# Sheet1.net
KiCad netlist of a schematic drawn in Altium Designer
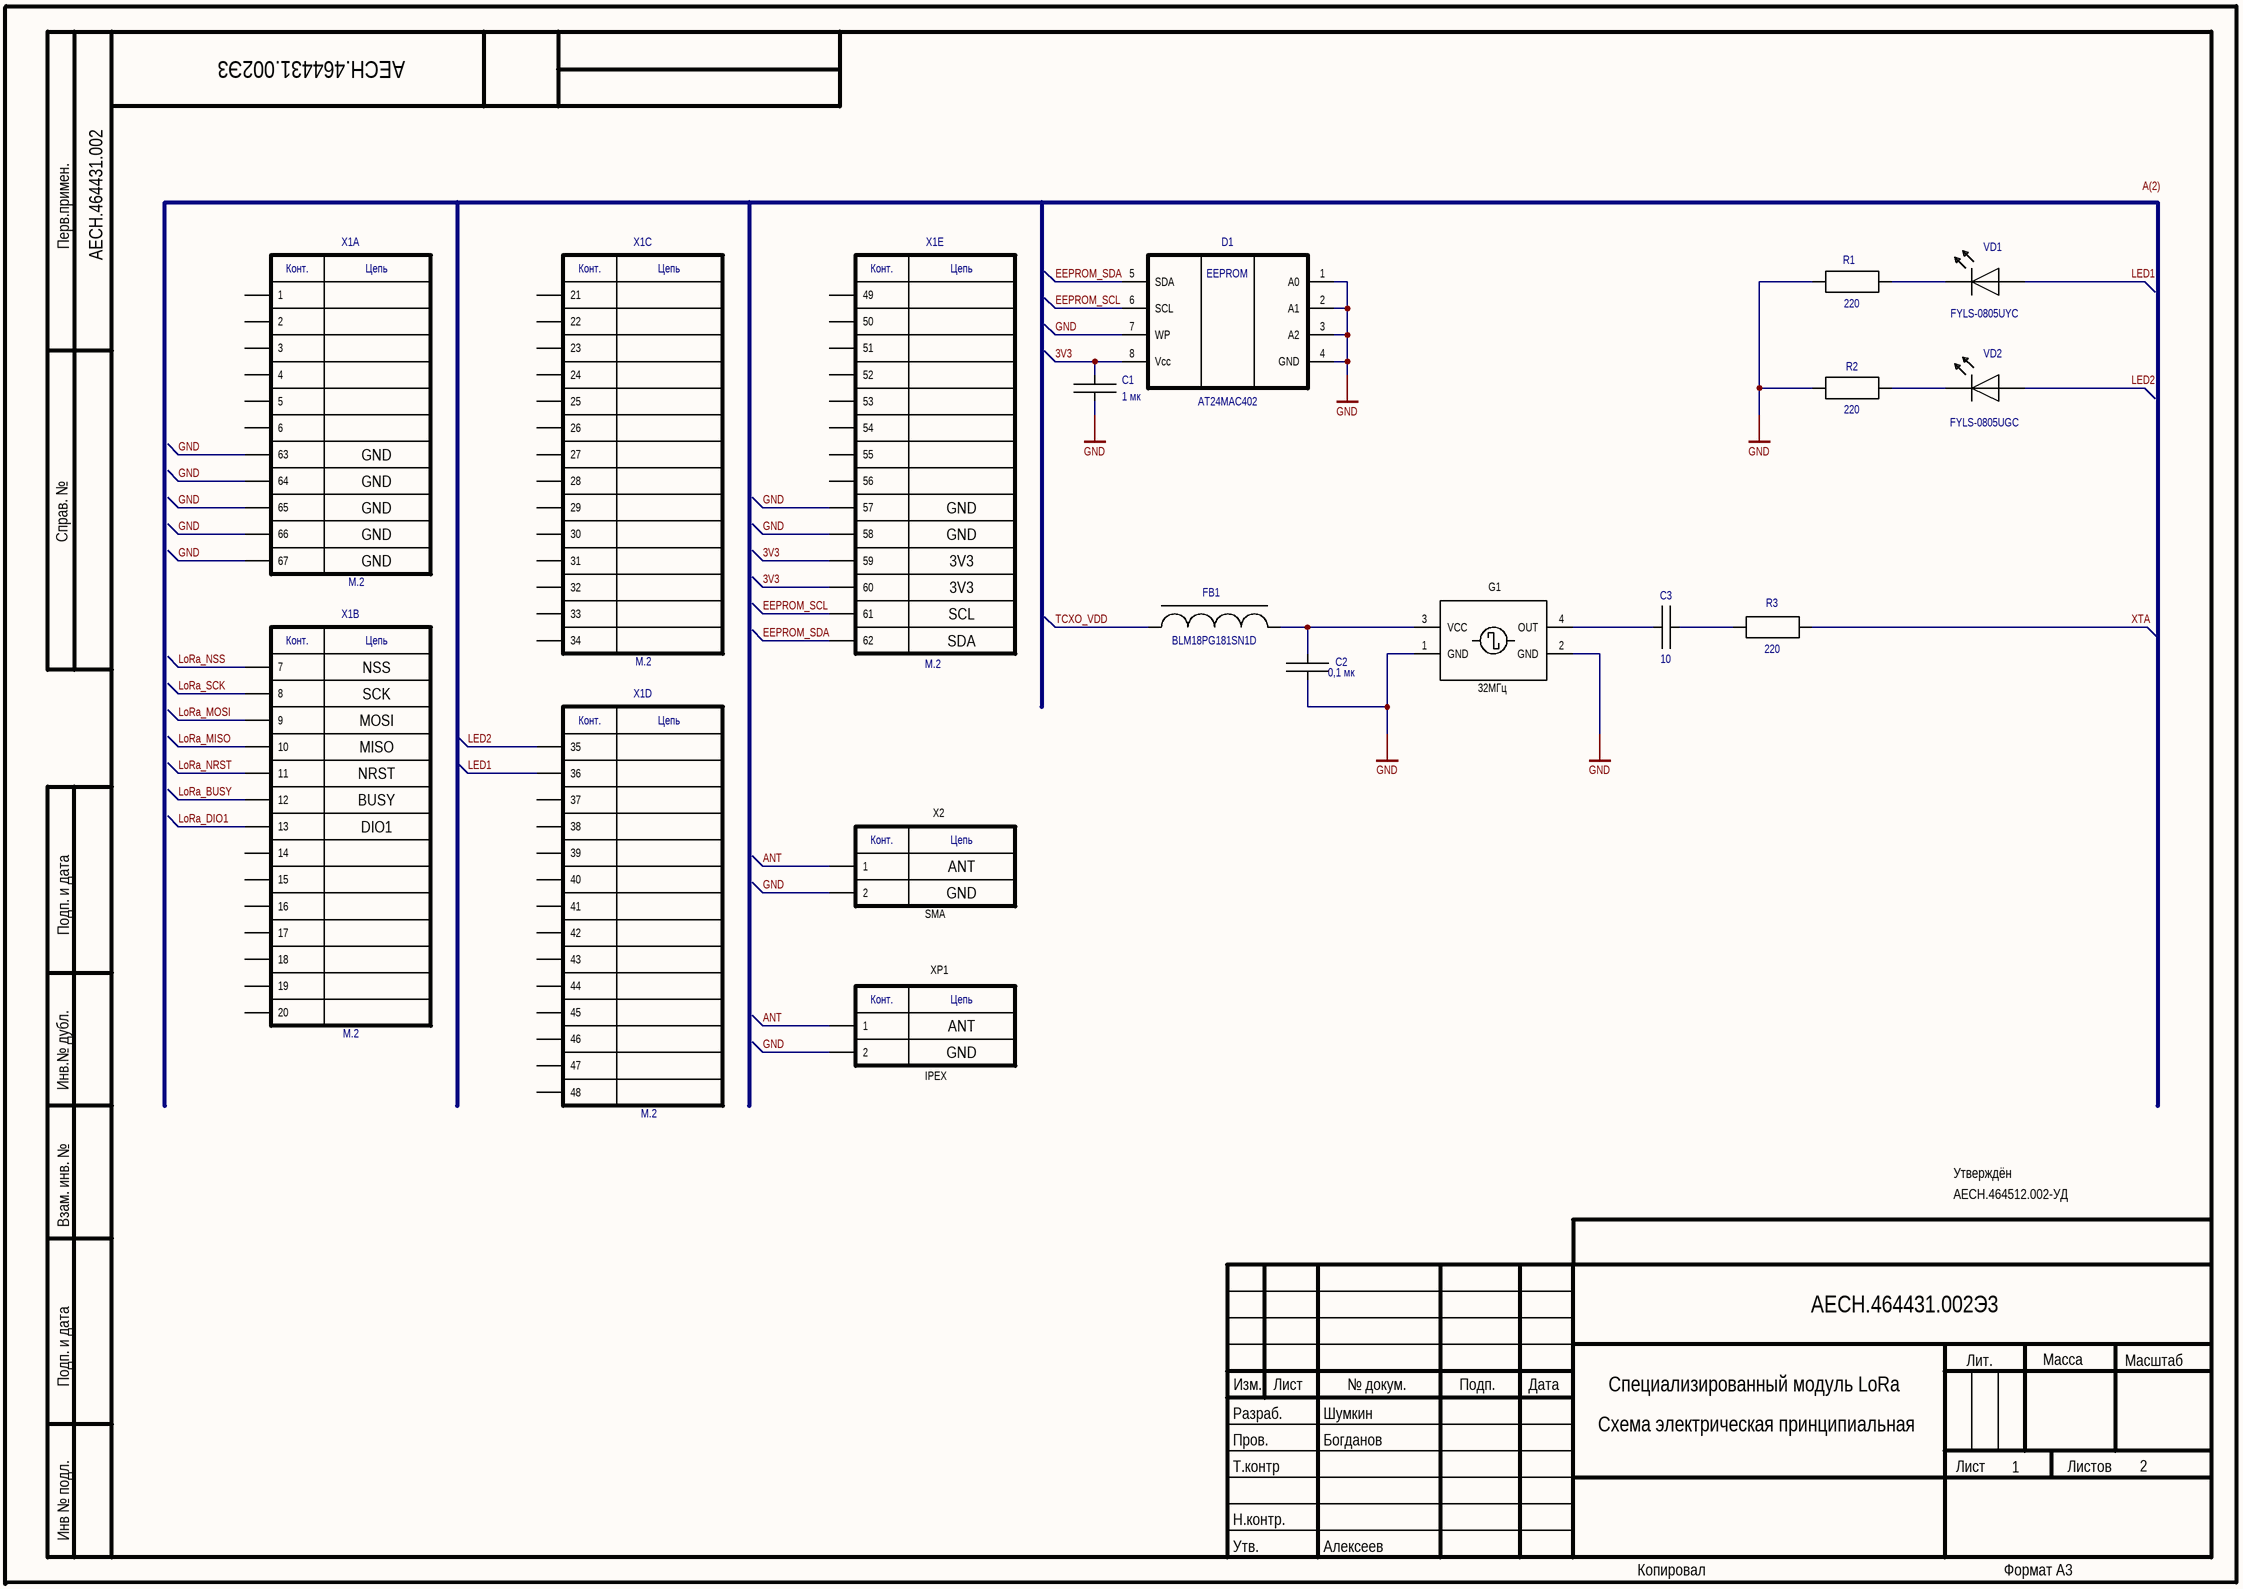
[diagram p0: Sheet1.SchDoc]

(export (version "E")
  (design (tool "Eeschema 10.0.6"))
  (components
    (comp (ref "C1")
      (value "1 мк")
      (footprint "С0603")
      (fields (field (name "VOLTAGE") "16 В") (field (name "Comment") "C"))
      (libsource (lib "Schlib1") (part "C"))
    )
    (comp (ref "C2")
      (value "0,1 мк")
      (footprint "С0603")
      (fields (field (name "VOLTAGE") "16 В") (field (name "Comment") "C"))
      (libsource (lib "Schlib1") (part "C"))
    )
    (comp (ref "C3")
      (value "10")
      (footprint "С0603")
      (fields (field (name "VOLTAGE") "50 В") (field (name "Comment") "C"))
      (libsource (lib "Schlib1") (part "C"))
    )
    (comp (ref "D1") (value "AT24MAC402") (footprint "SOIC8") (libsource (lib "Schlib1") (part "AT24MAC402")))
    (comp (ref "FB1")
      (value "BLM18PG181SN1D")
      (footprint "R0603")
      (fields (field (name "Comment") "Ferrite_Beads"))
      (libsource (lib "Schlib1") (part "Ferrite_Beads"))
    )
    (comp (ref "G1") (value "32МГц") (footprint "OSC_2016") (libsource (lib "Schlib1") (part "TCXO")))
    (comp (ref "R1")
      (value "220")
      (footprint "R0603")
      (fields (field (name "Comment") "R"))
      (libsource (lib "Schlib1") (part "R"))
    )
    (comp (ref "R2")
      (value "220")
      (footprint "R0603")
      (fields (field (name "Comment") "R"))
      (libsource (lib "Schlib1") (part "R"))
    )
    (comp (ref "R3")
      (value "220")
      (footprint "R0603")
      (fields (field (name "Comment") "R"))
      (libsource (lib "Schlib1") (part "R"))
    )
    (comp (ref "VD1")
      (value "FYLS-0805UYC")
      (footprint "LED_0805")
      (fields (field (name "VOLTAGE") "?"))
      (libsource (lib "Schlib1") (part "VD_LED"))
    )
    (comp (ref "VD2")
      (value "FYLS-0805UGC")
      (footprint "LED_0805")
      (fields (field (name "VOLTAGE") "?"))
      (libsource (lib "Schlib1") (part "VD_LED"))
    )
    (comp (ref "X1") (value "M.2") (footprint "M.2_edge") (libsource (lib "Schlib1") (part "M.2")))
    (comp (ref "X2") (value "SMA") (footprint "SMA_kont") (libsource (lib "Schlib1") (part "2pin")))
    (comp (ref "XP1") (value "IPEX") (footprint "IPEX") (libsource (lib "Schlib1") (part "2pin")))
  )
  (nets
    (net (code "1") (name "/3V3") (class "Default")
      (node (ref "C1") (pin "1") (pinfunction "1_1") (pintype "passive"))
      (node (ref "D1") (pin "8") (pinfunction "Vcc_8") (pintype "passive"))
      (node (ref "X1") (pin "59") (pinfunction "59_59") (pintype "passive"))
      (node (ref "X1") (pin "60") (pinfunction "60_60") (pintype "passive"))
    )
    (net (code "3") (name "/ANT") (class "Default")
      (node (ref "X2") (pin "1") (pinfunction "1_1") (pintype "passive"))
      (node (ref "XP1") (pin "1") (pinfunction "1_1") (pintype "passive"))
    )
    (net (code "4") (name "/EEPROM_SCL") (class "Default")
      (node (ref "D1") (pin "6") (pinfunction "SCL_6") (pintype "passive"))
      (node (ref "X1") (pin "61") (pinfunction "61_61") (pintype "passive"))
    )
    (net (code "5") (name "/EEPROM_SDA") (class "Default")
      (node (ref "D1") (pin "5") (pinfunction "SDA_5") (pintype "passive"))
      (node (ref "X1") (pin "62") (pinfunction "62_62") (pintype "passive"))
    )
    (net (code "6") (name "/LED1") (class "Default")
      (node (ref "VD1") (pin "1") (pinfunction "1_1") (pintype "passive"))
      (node (ref "X1") (pin "36") (pinfunction "36_36") (pintype "passive"))
    )
    (net (code "7") (name "/LED2") (class "Default")
      (node (ref "VD2") (pin "1") (pinfunction "1_1") (pintype "passive"))
      (node (ref "X1") (pin "35") (pinfunction "35_35") (pintype "passive"))
    )
    (net (code "8") (name "/LoRa_BUSY") (class "Default")
      (node (ref "X1") (pin "12") (pinfunction "12_12") (pintype "passive"))
    )
    (net (code "9") (name "/LoRa_DIO1") (class "Default")
      (node (ref "X1") (pin "13") (pinfunction "13_13") (pintype "passive"))
    )
    (net (code "10") (name "/LoRa_MISO") (class "Default")
      (node (ref "X1") (pin "10") (pinfunction "10_10") (pintype "passive"))
    )
    (net (code "11") (name "/LoRa_MOSI") (class "Default")
      (node (ref "X1") (pin "9") (pinfunction "9_9") (pintype "passive"))
    )
    (net (code "12") (name "/LoRa_NRST") (class "Default")
      (node (ref "X1") (pin "11") (pinfunction "11_11") (pintype "passive"))
    )
    (net (code "13") (name "/LoRa_NSS") (class "Default")
      (node (ref "X1") (pin "7") (pinfunction "7_7") (pintype "passive"))
    )
    (net (code "14") (name "/LoRa_SCK") (class "Default")
      (node (ref "X1") (pin "8") (pinfunction "8_8") (pintype "passive"))
    )
    (net (code "15") (name "/TCXO_VDD") (class "Default")
      (node (ref "FB1") (pin "1") (pinfunction "1_1") (pintype "passive"))
    )
    (net (code "16") (name "/XTA") (class "Default")
      (node (ref "R3") (pin "2") (pinfunction "2_2") (pintype "passive"))
    )
    (net (code "17") (name "GND") (class "Default")
      (node (ref "C1") (pin "2") (pinfunction "2_2") (pintype "passive"))
      (node (ref "C2") (pin "2") (pinfunction "2_2") (pintype "passive"))
      (node (ref "D1") (pin "1") (pinfunction "A0_1") (pintype "passive"))
      (node (ref "D1") (pin "2") (pinfunction "A1_2") (pintype "passive"))
      (node (ref "D1") (pin "3") (pinfunction "A2_3") (pintype "passive"))
      (node (ref "D1") (pin "4") (pinfunction "GND_4") (pintype "passive"))
      (node (ref "D1") (pin "7") (pinfunction "WP_7") (pintype "passive"))
      (node (ref "G1") (pin "1") (pinfunction "GND_1") (pintype "passive"))
      (node (ref "G1") (pin "2") (pinfunction "GND_2") (pintype "passive"))
      (node (ref "R1") (pin "2") (pinfunction "2_2") (pintype "passive"))
      (node (ref "R2") (pin "2") (pinfunction "2_2") (pintype "passive"))
      (node (ref "X1") (pin "57") (pinfunction "57_57") (pintype "passive"))
      (node (ref "X1") (pin "58") (pinfunction "58_58") (pintype "passive"))
      (node (ref "X1") (pin "63") (pinfunction "63_63") (pintype "passive"))
      (node (ref "X1") (pin "64") (pinfunction "64_64") (pintype "passive"))
      (node (ref "X1") (pin "65") (pinfunction "65_65") (pintype "passive"))
      (node (ref "X1") (pin "66") (pinfunction "66_66") (pintype "passive"))
      (node (ref "X1") (pin "67") (pinfunction "67_67") (pintype "passive"))
      (node (ref "X2") (pin "2") (pinfunction "2_2") (pintype "passive"))
      (node (ref "XP1") (pin "2") (pinfunction "2_2") (pintype "passive"))
    )
    (net (code "18") (name "Net-(C3-Pad2)") (class "Default")
      (node (ref "C3") (pin "2") (pinfunction "2_2") (pintype "passive"))
      (node (ref "R3") (pin "1") (pinfunction "1_1") (pintype "passive"))
    )
    (net (code "19") (name "Net-(G1-OUT)") (class "Default")
      (node (ref "C3") (pin "1") (pinfunction "1_1") (pintype "passive"))
      (node (ref "G1") (pin "4") (pinfunction "OUT_4") (pintype "passive"))
    )
    (net (code "20") (name "Net-(G1-VCC)") (class "Default")
      (node (ref "C2") (pin "1") (pinfunction "1_1") (pintype "passive"))
      (node (ref "FB1") (pin "2") (pinfunction "2_2") (pintype "passive"))
      (node (ref "G1") (pin "3") (pinfunction "VCC_3") (pintype "passive"))
    )
    (net (code "21") (name "Net-(R1-Pad1)") (class "Default")
      (node (ref "R1") (pin "1") (pinfunction "1_1") (pintype "passive"))
      (node (ref "VD1") (pin "2") (pinfunction "2_2") (pintype "passive"))
    )
    (net (code "22") (name "Net-(R2-Pad1)") (class "Default")
      (node (ref "R2") (pin "1") (pinfunction "1_1") (pintype "passive"))
      (node (ref "VD2") (pin "2") (pinfunction "2_2") (pintype "passive"))
    )
    (net (code "23") (name "unconnected-(X1-Pad1)") (class "Default")
      (node (ref "X1") (pin "1") (pinfunction "1_1") (pintype "passive"))
    )
    (net (code "24") (name "unconnected-(X1-Pad2)") (class "Default")
      (node (ref "X1") (pin "2") (pinfunction "2_2") (pintype "passive"))
    )
    (net (code "25") (name "unconnected-(X1-Pad3)") (class "Default")
      (node (ref "X1") (pin "3") (pinfunction "3_3") (pintype "passive"))
    )
    (net (code "26") (name "unconnected-(X1-Pad4)") (class "Default")
      (node (ref "X1") (pin "4") (pinfunction "4_4") (pintype "passive"))
    )
    (net (code "27") (name "unconnected-(X1-Pad5)") (class "Default")
      (node (ref "X1") (pin "5") (pinfunction "5_5") (pintype "passive"))
    )
    (net (code "28") (name "unconnected-(X1-Pad6)") (class "Default")
      (node (ref "X1") (pin "6") (pinfunction "6_6") (pintype "passive"))
    )
    (net (code "29") (name "unconnected-(X1-Pad14)") (class "Default")
      (node (ref "X1") (pin "14") (pinfunction "14_14") (pintype "passive"))
    )
    (net (code "30") (name "unconnected-(X1-Pad15)") (class "Default")
      (node (ref "X1") (pin "15") (pinfunction "15_15") (pintype "passive"))
    )
    (net (code "31") (name "unconnected-(X1-Pad16)") (class "Default")
      (node (ref "X1") (pin "16") (pinfunction "16_16") (pintype "passive"))
    )
    (net (code "32") (name "unconnected-(X1-Pad17)") (class "Default")
      (node (ref "X1") (pin "17") (pinfunction "17_17") (pintype "passive"))
    )
    (net (code "33") (name "unconnected-(X1-Pad18)") (class "Default")
      (node (ref "X1") (pin "18") (pinfunction "18_18") (pintype "passive"))
    )
    (net (code "34") (name "unconnected-(X1-Pad19)") (class "Default")
      (node (ref "X1") (pin "19") (pinfunction "19_19") (pintype "passive"))
    )
    (net (code "35") (name "unconnected-(X1-Pad20)") (class "Default")
      (node (ref "X1") (pin "20") (pinfunction "20_20") (pintype "passive"))
    )
    (net (code "36") (name "unconnected-(X1-Pad21)") (class "Default")
      (node (ref "X1") (pin "21") (pinfunction "21_21") (pintype "passive"))
    )
    (net (code "37") (name "unconnected-(X1-Pad22)") (class "Default")
      (node (ref "X1") (pin "22") (pinfunction "22_22") (pintype "passive"))
    )
    (net (code "38") (name "unconnected-(X1-Pad23)") (class "Default")
      (node (ref "X1") (pin "23") (pinfunction "23_23") (pintype "passive"))
    )
    (net (code "39") (name "unconnected-(X1-Pad24)") (class "Default")
      (node (ref "X1") (pin "24") (pinfunction "24_24") (pintype "passive"))
    )
    (net (code "40") (name "unconnected-(X1-Pad25)") (class "Default")
      (node (ref "X1") (pin "25") (pinfunction "25_25") (pintype "passive"))
    )
    (net (code "41") (name "unconnected-(X1-Pad26)") (class "Default")
      (node (ref "X1") (pin "26") (pinfunction "26_26") (pintype "passive"))
    )
    (net (code "42") (name "unconnected-(X1-Pad27)") (class "Default")
      (node (ref "X1") (pin "27") (pinfunction "27_27") (pintype "passive"))
    )
    (net (code "43") (name "unconnected-(X1-Pad28)") (class "Default")
      (node (ref "X1") (pin "28") (pinfunction "28_28") (pintype "passive"))
    )
    (net (code "44") (name "unconnected-(X1-Pad29)") (class "Default")
      (node (ref "X1") (pin "29") (pinfunction "29_29") (pintype "passive"))
    )
    (net (code "45") (name "unconnected-(X1-Pad30)") (class "Default")
      (node (ref "X1") (pin "30") (pinfunction "30_30") (pintype "passive"))
    )
    (net (code "46") (name "unconnected-(X1-Pad31)") (class "Default")
      (node (ref "X1") (pin "31") (pinfunction "31_31") (pintype "passive"))
    )
    (net (code "47") (name "unconnected-(X1-Pad32)") (class "Default")
      (node (ref "X1") (pin "32") (pinfunction "32_32") (pintype "passive"))
    )
    (net (code "48") (name "unconnected-(X1-Pad33)") (class "Default")
      (node (ref "X1") (pin "33") (pinfunction "33_33") (pintype "passive"))
    )
    (net (code "49") (name "unconnected-(X1-Pad34)") (class "Default")
      (node (ref "X1") (pin "34") (pinfunction "34_34") (pintype "passive"))
    )
    (net (code "50") (name "unconnected-(X1-Pad37)") (class "Default")
      (node (ref "X1") (pin "37") (pinfunction "37_37") (pintype "passive"))
    )
    (net (code "51") (name "unconnected-(X1-Pad38)") (class "Default")
      (node (ref "X1") (pin "38") (pinfunction "38_38") (pintype "passive"))
    )
    (net (code "52") (name "unconnected-(X1-Pad39)") (class "Default")
      (node (ref "X1") (pin "39") (pinfunction "39_39") (pintype "passive"))
    )
    (net (code "53") (name "unconnected-(X1-Pad40)") (class "Default")
      (node (ref "X1") (pin "40") (pinfunction "40_40") (pintype "passive"))
    )
    (net (code "54") (name "unconnected-(X1-Pad41)") (class "Default")
      (node (ref "X1") (pin "41") (pinfunction "41_41") (pintype "passive"))
    )
    (net (code "55") (name "unconnected-(X1-Pad42)") (class "Default")
      (node (ref "X1") (pin "42") (pinfunction "42_42") (pintype "passive"))
    )
    (net (code "56") (name "unconnected-(X1-Pad43)") (class "Default")
      (node (ref "X1") (pin "43") (pinfunction "43_43") (pintype "passive"))
    )
    (net (code "57") (name "unconnected-(X1-Pad44)") (class "Default")
      (node (ref "X1") (pin "44") (pinfunction "44_44") (pintype "passive"))
    )
    (net (code "58") (name "unconnected-(X1-Pad45)") (class "Default")
      (node (ref "X1") (pin "45") (pinfunction "45_45") (pintype "passive"))
    )
    (net (code "59") (name "unconnected-(X1-Pad46)") (class "Default")
      (node (ref "X1") (pin "46") (pinfunction "46_46") (pintype "passive"))
    )
    (net (code "60") (name "unconnected-(X1-Pad47)") (class "Default")
      (node (ref "X1") (pin "47") (pinfunction "47_47") (pintype "passive"))
    )
    (net (code "61") (name "unconnected-(X1-Pad48)") (class "Default")
      (node (ref "X1") (pin "48") (pinfunction "48_48") (pintype "passive"))
    )
    (net (code "62") (name "unconnected-(X1-Pad49)") (class "Default")
      (node (ref "X1") (pin "49") (pinfunction "49_49") (pintype "passive"))
    )
    (net (code "63") (name "unconnected-(X1-Pad50)") (class "Default")
      (node (ref "X1") (pin "50") (pinfunction "50_50") (pintype "passive"))
    )
    (net (code "64") (name "unconnected-(X1-Pad51)") (class "Default")
      (node (ref "X1") (pin "51") (pinfunction "51_51") (pintype "passive"))
    )
    (net (code "65") (name "unconnected-(X1-Pad52)") (class "Default")
      (node (ref "X1") (pin "52") (pinfunction "52_52") (pintype "passive"))
    )
    (net (code "66") (name "unconnected-(X1-Pad53)") (class "Default")
      (node (ref "X1") (pin "53") (pinfunction "53_53") (pintype "passive"))
    )
    (net (code "67") (name "unconnected-(X1-Pad54)") (class "Default")
      (node (ref "X1") (pin "54") (pinfunction "54_54") (pintype "passive"))
    )
    (net (code "68") (name "unconnected-(X1-Pad55)") (class "Default")
      (node (ref "X1") (pin "55") (pinfunction "55_55") (pintype "passive"))
    )
    (net (code "69") (name "unconnected-(X1-Pad56)") (class "Default")
      (node (ref "X1") (pin "56") (pinfunction "56_56") (pintype "passive"))
    )
  )
)
